# ISPnub_v1_0.net
KiCad netlist of a schematic drawn in EAGLE
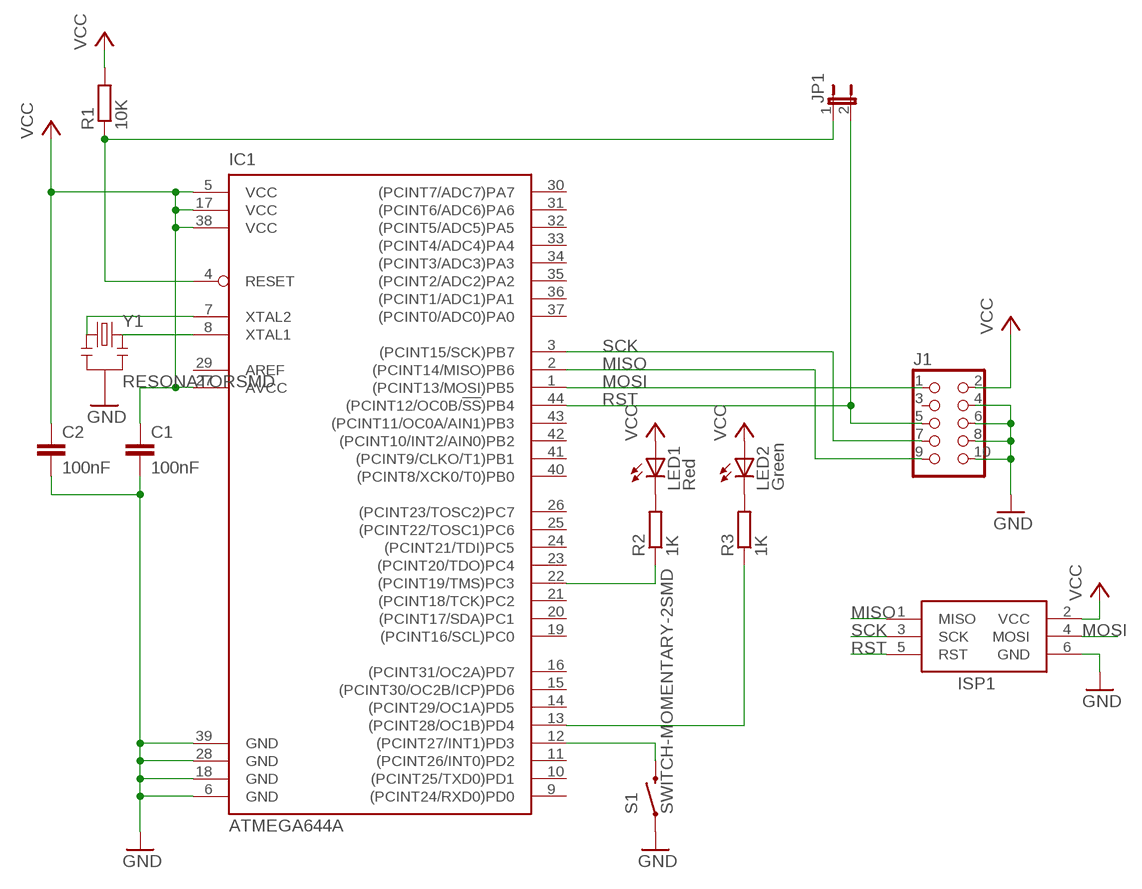
[diagram p0: schematic, sheet 1]

(export (version "E")
  (design (tool "Eeschema 10.0.6"))
  (components
    (comp (ref "C1")
      (value "100nF")
      (footprint "eagle-import:C0805")
      (libsource (lib "eagle-import") (part "C-EUC0805"))
    )
    (comp (ref "C2")
      (value "100nF")
      (footprint "eagle-import:C0805")
      (libsource (lib "eagle-import") (part "C-EUC0805"))
    )
    (comp (ref "IC1")
      (value "ATMEGA644A")
      (footprint "eagle-import:TQFP44")
      (fields (field (name "MPN") "ATMEGA644PV-10AU") (field (name "MPN_1") "ATMEGA1284PV-10AU"))
      (libsource (lib "eagle-import") (part "ATMEGA644A"))
    )
    (comp (ref "ISP1")
      (value "AVRISP-BOX")
      (footprint "eagle-import:AVRISP-BOX")
      (libsource (lib "eagle-import") (part "AVRISP-BOX"))
    )
    (comp (ref "J1")
      (value "CON_HEADER_2X05-PTH+SHROUDED_A")
      (footprint "eagle-import:PINSHRD_PTH_2X05")
      (libsource (lib "eagle-import") (part "CON_HEADER_2X05-PTH+SHROUDED_A"))
    )
    (comp (ref "JP1")
      (value "JP1E")
      (footprint "eagle-import:JP1")
      (libsource (lib "eagle-import") (part "JP1E"))
    )
    (comp (ref "LED1")
      (value "Red")
      (footprint "eagle-import:CHIP-LED0805")
      (libsource (lib "eagle-import") (part "LEDCHIP-LED0805"))
    )
    (comp (ref "LED2")
      (value "Green")
      (footprint "eagle-import:CHIP-LED0805")
      (libsource (lib "eagle-import") (part "LEDCHIP-LED0805"))
    )
    (comp (ref "R1")
      (value "10K")
      (footprint "eagle-import:R0805")
      (libsource (lib "eagle-import") (part "R-EU_R0805"))
    )
    (comp (ref "R2")
      (value "1K")
      (footprint "eagle-import:R0805")
      (libsource (lib "eagle-import") (part "R-EU_R0805"))
    )
    (comp (ref "R3")
      (value "1K")
      (footprint "eagle-import:R0805")
      (libsource (lib "eagle-import") (part "R-EU_R0805"))
    )
    (comp (ref "S1")
      (value "SWITCH-MOMENTARY-2SMD")
      (footprint "eagle-import:TACTILE_SWITCH_SMD")
      (libsource (lib "eagle-import") (part "SWITCH-MOMENTARY-2SMD"))
    )
    (comp (ref "Y1")
      (value "RESONATORSMD")
      (footprint "eagle-import:RESONATOR-SMD")
      (libsource (lib "eagle-import") (part "RESONATORSMD"))
    )
  )
  (nets
    (net (code "1") (name "/MISO") (class "Default")
      (node (ref "IC1") (pin "2") (pinfunction "(PCINT14/MISO)PB6_2") (pintype "bidirectional"))
      (node (ref "ISP1") (pin "1") (pinfunction "MISO_1") (pintype "input"))
      (node (ref "J1") (pin "9") (pinfunction "9_9") (pintype "passive"))
    )
    (net (code "2") (name "/MOSI") (class "Default")
      (node (ref "IC1") (pin "1") (pinfunction "(PCINT13/MOSI)PB5_1") (pintype "bidirectional"))
      (node (ref "ISP1") (pin "4") (pinfunction "MOSI_4") (pintype "output"))
      (node (ref "J1") (pin "1") (pinfunction "1_1") (pintype "passive"))
    )
    (net (code "3") (name "/RST") (class "Default")
      (node (ref "IC1") (pin "44") (pinfunction "(PCINT12/OC0B/~{SS})PB4_44") (pintype "bidirectional"))
      (node (ref "ISP1") (pin "5") (pinfunction "RST_5") (pintype "output"))
      (node (ref "J1") (pin "5") (pinfunction "5_5") (pintype "passive"))
      (node (ref "JP1") (pin "2") (pinfunction "2_2") (pintype "passive"))
    )
    (net (code "4") (name "/SCK") (class "Default")
      (node (ref "IC1") (pin "3") (pinfunction "(PCINT15/SCK)PB7_3") (pintype "bidirectional"))
      (node (ref "ISP1") (pin "3") (pinfunction "SCK_3") (pintype "output"))
      (node (ref "J1") (pin "7") (pinfunction "7_7") (pintype "passive"))
    )
    (net (code "5") (name "GND") (class "Default")
      (node (ref "C1") (pin "2") (pinfunction "2_2") (pintype "passive"))
      (node (ref "C2") (pin "2") (pinfunction "2_2") (pintype "passive"))
      (node (ref "IC1") (pin "18") (pinfunction "GND_18") (pintype "power_in"))
      (node (ref "IC1") (pin "28") (pinfunction "GND_28") (pintype "power_in"))
      (node (ref "IC1") (pin "39") (pinfunction "GND_39") (pintype "power_in"))
      (node (ref "IC1") (pin "6") (pinfunction "GND_6") (pintype "power_in"))
      (node (ref "ISP1") (pin "6") (pinfunction "GND_6") (pintype "power_in"))
      (node (ref "J1") (pin "10") (pinfunction "10_10") (pintype "passive"))
      (node (ref "J1") (pin "4") (pinfunction "4_4") (pintype "passive"))
      (node (ref "J1") (pin "6") (pinfunction "6_6") (pintype "passive"))
      (node (ref "J1") (pin "8") (pinfunction "8_8") (pintype "passive"))
      (node (ref "S1") (pin "1") (pinfunction "1_1") (pintype "passive"))
      (node (ref "Y1") (pin "2") (pinfunction "2_2") (pintype "passive"))
    )
    (net (code "6") (name "Net-(IC1-(PCINT19{slash}TMS)PC3)") (class "Default")
      (node (ref "IC1") (pin "22") (pinfunction "(PCINT19/TMS)PC3_22") (pintype "output"))
      (node (ref "R2") (pin "1") (pinfunction "1_1") (pintype "passive"))
    )
    (net (code "7") (name "Net-(IC1-(PCINT27{slash}INT1)PD3)") (class "Default")
      (node (ref "IC1") (pin "12") (pinfunction "(PCINT27/INT1)PD3_12") (pintype "bidirectional"))
      (node (ref "S1") (pin "3") (pinfunction "2_3") (pintype "passive"))
    )
    (net (code "8") (name "Net-(IC1-(PCINT28{slash}OC1B)PD4)") (class "Default")
      (node (ref "IC1") (pin "13") (pinfunction "(PCINT28/OC1B)PD4_13") (pintype "bidirectional"))
      (node (ref "R3") (pin "1") (pinfunction "1_1") (pintype "passive"))
    )
    (net (code "9") (name "Net-(IC1-RESET)") (class "Default")
      (node (ref "IC1") (pin "4") (pinfunction "RESET_4") (pintype "input"))
      (node (ref "JP1") (pin "1") (pinfunction "1_1") (pintype "passive"))
      (node (ref "R1") (pin "1") (pinfunction "1_1") (pintype "passive"))
    )
    (net (code "10") (name "Net-(IC1-XTAL1)") (class "Default")
      (node (ref "IC1") (pin "8") (pinfunction "XTAL1_8") (pintype "bidirectional"))
      (node (ref "Y1") (pin "3") (pinfunction "3_3") (pintype "passive"))
    )
    (net (code "11") (name "Net-(IC1-XTAL2)") (class "Default")
      (node (ref "IC1") (pin "7") (pinfunction "XTAL2_7") (pintype "bidirectional"))
      (node (ref "Y1") (pin "1") (pinfunction "1_1") (pintype "passive"))
    )
    (net (code "12") (name "Net-(LED1-PadC)") (class "Default")
      (node (ref "LED1") (pin "C") (pinfunction "C_C") (pintype "passive"))
      (node (ref "R2") (pin "2") (pinfunction "2_2") (pintype "passive"))
    )
    (net (code "13") (name "Net-(LED2-PadC)") (class "Default")
      (node (ref "LED2") (pin "C") (pinfunction "C_C") (pintype "passive"))
      (node (ref "R3") (pin "2") (pinfunction "2_2") (pintype "passive"))
    )
    (net (code "14") (name "VCC") (class "Default")
      (node (ref "C1") (pin "1") (pinfunction "1_1") (pintype "passive"))
      (node (ref "C2") (pin "1") (pinfunction "1_1") (pintype "passive"))
      (node (ref "IC1") (pin "17") (pinfunction "VCC_17") (pintype "power_in"))
      (node (ref "IC1") (pin "27") (pinfunction "AVCC_27") (pintype "power_in"))
      (node (ref "IC1") (pin "38") (pinfunction "VCC_38") (pintype "power_in"))
      (node (ref "IC1") (pin "5") (pinfunction "VCC_5") (pintype "power_in"))
      (node (ref "ISP1") (pin "2") (pinfunction "VCC_2") (pintype "power_in"))
      (node (ref "J1") (pin "2") (pinfunction "2_2") (pintype "passive"))
      (node (ref "LED1") (pin "A") (pinfunction "A_A") (pintype "passive"))
      (node (ref "LED2") (pin "A") (pinfunction "A_A") (pintype "passive"))
      (node (ref "R1") (pin "2") (pinfunction "2_2") (pintype "passive"))
    )
    (net (code "15") (name "unconnected-(IC1-(PCINT0{slash}ADC0)PA0-Pad37)") (class "Default")
      (node (ref "IC1") (pin "37") (pinfunction "(PCINT0/ADC0)PA0_37") (pintype "bidirectional"))
    )
    (net (code "16") (name "unconnected-(IC1-(PCINT1{slash}ADC1)PA1-Pad36)") (class "Default")
      (node (ref "IC1") (pin "36") (pinfunction "(PCINT1/ADC1)PA1_36") (pintype "bidirectional"))
    )
    (net (code "17") (name "unconnected-(IC1-(PCINT2{slash}ADC2)PA2-Pad35)") (class "Default")
      (node (ref "IC1") (pin "35") (pinfunction "(PCINT2/ADC2)PA2_35") (pintype "bidirectional"))
    )
    (net (code "18") (name "unconnected-(IC1-(PCINT3{slash}ADC3)PA3-Pad34)") (class "Default")
      (node (ref "IC1") (pin "34") (pinfunction "(PCINT3/ADC3)PA3_34") (pintype "bidirectional"))
    )
    (net (code "19") (name "unconnected-(IC1-(PCINT4{slash}ADC4)PA4-Pad33)") (class "Default")
      (node (ref "IC1") (pin "33") (pinfunction "(PCINT4/ADC4)PA4_33") (pintype "bidirectional"))
    )
    (net (code "20") (name "unconnected-(IC1-(PCINT5{slash}ADC5)PA5-Pad32)") (class "Default")
      (node (ref "IC1") (pin "32") (pinfunction "(PCINT5/ADC5)PA5_32") (pintype "bidirectional"))
    )
    (net (code "21") (name "unconnected-(IC1-(PCINT6{slash}ADC6)PA6-Pad31)") (class "Default")
      (node (ref "IC1") (pin "31") (pinfunction "(PCINT6/ADC6)PA6_31") (pintype "bidirectional"))
    )
    (net (code "22") (name "unconnected-(IC1-(PCINT7{slash}ADC7)PA7-Pad30)") (class "Default")
      (node (ref "IC1") (pin "30") (pinfunction "(PCINT7/ADC7)PA7_30") (pintype "bidirectional"))
    )
    (net (code "23") (name "unconnected-(IC1-(PCINT8{slash}XCK0{slash}T0)PB0-Pad40)") (class "Default")
      (node (ref "IC1") (pin "40") (pinfunction "(PCINT8/XCK0/T0)PB0_40") (pintype "bidirectional"))
    )
    (net (code "24") (name "unconnected-(IC1-(PCINT9{slash}CLKO{slash}T1)PB1-Pad41)") (class "Default")
      (node (ref "IC1") (pin "41") (pinfunction "(PCINT9/CLKO/T1)PB1_41") (pintype "bidirectional"))
    )
    (net (code "25") (name "unconnected-(IC1-(PCINT10{slash}INT2{slash}AIN0)PB2-Pad42)") (class "Default")
      (node (ref "IC1") (pin "42") (pinfunction "(PCINT10/INT2/AIN0)PB2_42") (pintype "bidirectional"))
    )
    (net (code "26") (name "unconnected-(IC1-(PCINT11{slash}OC0A{slash}AIN1)PB3-Pad43)") (class "Default")
      (node (ref "IC1") (pin "43") (pinfunction "(PCINT11/OC0A/AIN1)PB3_43") (pintype "bidirectional"))
    )
    (net (code "27") (name "unconnected-(IC1-(PCINT16{slash}SCL)PC0-Pad19)") (class "Default")
      (node (ref "IC1") (pin "19") (pinfunction "(PCINT16/SCL)PC0_19") (pintype "output"))
    )
    (net (code "28") (name "unconnected-(IC1-(PCINT17{slash}SDA)PC1-Pad20)") (class "Default")
      (node (ref "IC1") (pin "20") (pinfunction "(PCINT17/SDA)PC1_20") (pintype "output"))
    )
    (net (code "29") (name "unconnected-(IC1-(PCINT18{slash}TCK)PC2-Pad21)") (class "Default")
      (node (ref "IC1") (pin "21") (pinfunction "(PCINT18/TCK)PC2_21") (pintype "output"))
    )
    (net (code "30") (name "unconnected-(IC1-(PCINT20{slash}TDO)PC4-Pad23)") (class "Default")
      (node (ref "IC1") (pin "23") (pinfunction "(PCINT20/TDO)PC4_23") (pintype "output"))
    )
    (net (code "31") (name "unconnected-(IC1-(PCINT21{slash}TDI)PC5-Pad24)") (class "Default")
      (node (ref "IC1") (pin "24") (pinfunction "(PCINT21/TDI)PC5_24") (pintype "output"))
    )
    (net (code "32") (name "unconnected-(IC1-(PCINT22{slash}TOSC1)PC6-Pad25)") (class "Default")
      (node (ref "IC1") (pin "25") (pinfunction "(PCINT22/TOSC1)PC6_25") (pintype "output"))
    )
    (net (code "33") (name "unconnected-(IC1-(PCINT23{slash}TOSC2)PC7-Pad26)") (class "Default")
      (node (ref "IC1") (pin "26") (pinfunction "(PCINT23/TOSC2)PC7_26") (pintype "output"))
    )
    (net (code "34") (name "unconnected-(IC1-(PCINT24{slash}RXD0)PD0-Pad9)") (class "Default")
      (node (ref "IC1") (pin "9") (pinfunction "(PCINT24/RXD0)PD0_9") (pintype "bidirectional"))
    )
    (net (code "35") (name "unconnected-(IC1-(PCINT25{slash}TXD0)PD1-Pad10)") (class "Default")
      (node (ref "IC1") (pin "10") (pinfunction "(PCINT25/TXD0)PD1_10") (pintype "bidirectional"))
    )
    (net (code "36") (name "unconnected-(IC1-(PCINT26{slash}INT0)PD2-Pad11)") (class "Default")
      (node (ref "IC1") (pin "11") (pinfunction "(PCINT26/INT0)PD2_11") (pintype "bidirectional"))
    )
    (net (code "37") (name "unconnected-(IC1-(PCINT29{slash}OC1A)PD5-Pad14)") (class "Default")
      (node (ref "IC1") (pin "14") (pinfunction "(PCINT29/OC1A)PD5_14") (pintype "bidirectional"))
    )
    (net (code "38") (name "unconnected-(IC1-(PCINT30{slash}OC2B{slash}ICP)PD6-Pad15)") (class "Default")
      (node (ref "IC1") (pin "15") (pinfunction "(PCINT30/OC2B/ICP)PD6_15") (pintype "bidirectional"))
    )
    (net (code "39") (name "unconnected-(IC1-(PCINT31{slash}OC2A)PD7-Pad16)") (class "Default")
      (node (ref "IC1") (pin "16") (pinfunction "(PCINT31/OC2A)PD7_16") (pintype "bidirectional"))
    )
    (net (code "40") (name "unconnected-(IC1-AREF-Pad29)") (class "Default")
      (node (ref "IC1") (pin "29") (pinfunction "AREF_29") (pintype "passive"))
    )
    (net (code "41") (name "unconnected-(J1-Pad3)") (class "Default")
      (node (ref "J1") (pin "3") (pinfunction "3_3") (pintype "passive"))
    )
  )
)
